# TrinketBlinkM0L.net
KiCad netlist of a schematic drawn in EAGLE
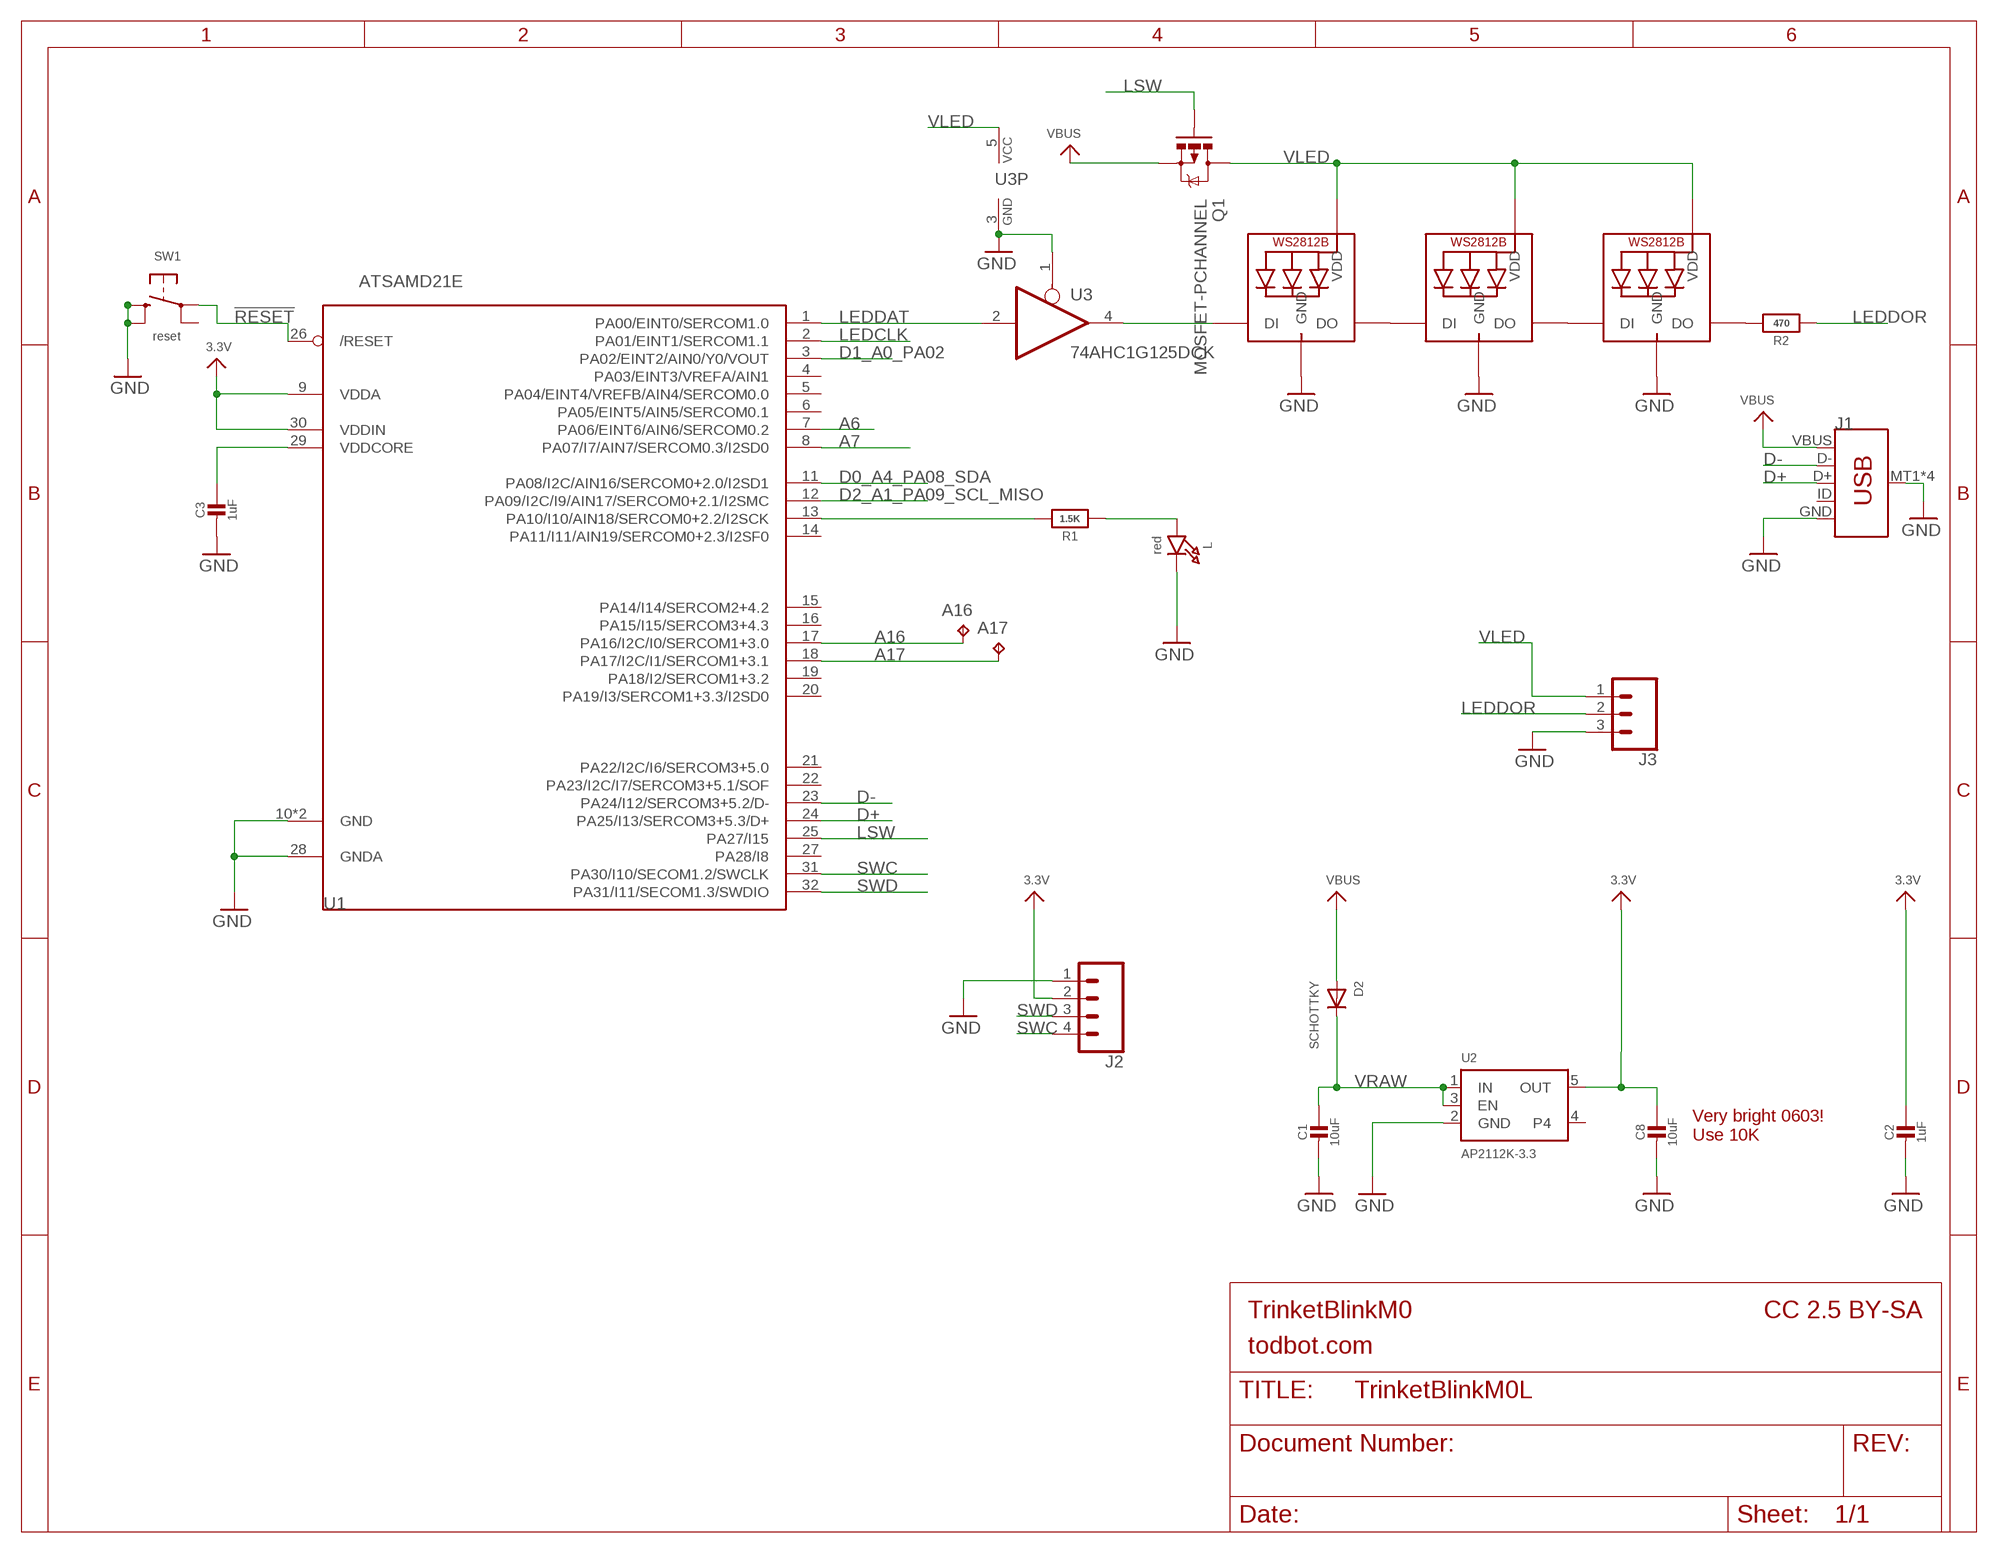
[diagram p0: schematic, sheet 1]

(export (version "E")
  (design (tool "Eeschema 10.0.6"))
  (components
    (comp (ref "A16")
      (value "TPB1,27")
      (footprint "eagle-import:B1,27")
      (libsource (lib "eagle-import") (part "TPB1,27"))
    )
    (comp (ref "A17")
      (value "TPB1,27")
      (footprint "eagle-import:B1,27")
      (libsource (lib "eagle-import") (part "TPB1,27"))
    )
    (comp (ref "C1")
      (value "10uF")
      (footprint "eagle-import:0805-NO")
      (libsource (lib "eagle-import") (part "CAP_CERAMIC0805-NOOUTLINE"))
    )
    (comp (ref "C2")
      (value "1uF")
      (footprint "eagle-import:0603-NO")
      (libsource (lib "eagle-import") (part "CAP_CERAMIC0603_NO"))
    )
    (comp (ref "C3")
      (value "1uF")
      (footprint "eagle-import:0603-NO")
      (libsource (lib "eagle-import") (part "CAP_CERAMIC0603_NO"))
    )
    (comp (ref "C8")
      (value "10uF")
      (footprint "eagle-import:0805-NO")
      (libsource (lib "eagle-import") (part "CAP_CERAMIC0805-NOOUTLINE"))
    )
    (comp (ref "D2")
      (value "SCHOTTKY")
      (footprint "eagle-import:SOD-123FL")
      (libsource (lib "eagle-import") (part "DIODE_SOD-123FL"))
    )
    (comp (ref "J1")
      (value "USB_MICRO-B_SMT")
      (footprint "eagle-import:USB-MICROB")
      (libsource (lib "eagle-import") (part "USB_MICRO-B_SMT"))
    )
    (comp (ref "J2")
      (value "CONN_04")
      (footprint "eagle-import:1X04")
      (libsource (lib "eagle-import") (part "CONN_04"))
    )
    (comp (ref "J3")
      (value "CONN_03")
      (footprint "eagle-import:1X03")
      (libsource (lib "eagle-import") (part "CONN_03"))
    )
    (comp (ref "L")
      (value "red")
      (footprint "eagle-import:CHIPLED_0603_NOOUTLINE")
      (libsource (lib "eagle-import") (part "LED0603_NOOUTLINE"))
    )
    (comp (ref "LED1")
      (value "WS2812B3535")
      (footprint "eagle-import:LED3535")
      (libsource (lib "eagle-import") (part "WS2812B3535"))
    )
    (comp (ref "LED2")
      (value "WS2812B3535")
      (footprint "eagle-import:LED3535")
      (libsource (lib "eagle-import") (part "WS2812B3535"))
    )
    (comp (ref "LED3")
      (value "WS2812B3535")
      (footprint "eagle-import:LED3535")
      (libsource (lib "eagle-import") (part "WS2812B3535"))
    )
    (comp (ref "Q1")
      (value "MOSFET-PCHANNEL")
      (footprint "eagle-import:SOT23-3")
      (libsource (lib "eagle-import") (part "MOSFET-PCHANNEL"))
    )
    (comp (ref "R1")
      (value "1.5K")
      (footprint "eagle-import:0603-NO")
      (libsource (lib "eagle-import") (part "RESISTOR_0603_NOOUT"))
    )
    (comp (ref "R2")
      (value "470")
      (footprint "eagle-import:0603-NO")
      (libsource (lib "eagle-import") (part "RESISTOR_0603_NOOUT"))
    )
    (comp (ref "SW1")
      (value "reset")
      (footprint "eagle-import:BTN_KMR2_4.6X2.8")
      (libsource (lib "eagle-import") (part "SWITCH_TACT_SMT4.6X2.8"))
    )
    (comp (ref "U1")
      (value "ATSAMD21E")
      (footprint "eagle-import:QFN32_5MM")
      (libsource (lib "eagle-import") (part "ATSAMD21E"))
    )
    (comp (ref "U2")
      (value "AP2112K-3.3")
      (footprint "eagle-import:SOT23-5")
      (libsource (lib "eagle-import") (part "VREG_SOT23-5"))
    )
    (comp (ref "U3")
      (value "74AHC1G125DCK")
      (footprint "eagle-import:SC70-5")
      (libsource (lib "eagle-import") (part "741G125DCKAHC"))
    )
  )
  (nets
    (net (code "1") (name "/A6") (class "Default")
      (node (ref "U1") (pin "7") (pinfunction "PA06/EINT6/AIN6/SERCOM0.2_7") (pintype "bidirectional"))
    )
    (net (code "2") (name "/A7") (class "Default")
      (node (ref "U1") (pin "8") (pinfunction "PA07/I7/AIN7/SERCOM0.3/I2SD0_8") (pintype "bidirectional"))
    )
    (net (code "3") (name "/A16") (class "Default")
      (node (ref "A16") (pin "TP") (pinfunction "TP_TP") (pintype "input"))
      (node (ref "U1") (pin "17") (pinfunction "PA16/I2C/I0/SERCOM1+3.0_17") (pintype "bidirectional"))
    )
    (net (code "4") (name "/A17") (class "Default")
      (node (ref "A17") (pin "TP") (pinfunction "TP_TP") (pintype "input"))
      (node (ref "U1") (pin "18") (pinfunction "PA17/I2C/I1/SERCOM1+3.1_18") (pintype "bidirectional"))
    )
    (net (code "5") (name "/D+") (class "Default")
      (node (ref "J1") (pin "D+") (pinfunction "D+_D+") (pintype "bidirectional"))
      (node (ref "U1") (pin "24") (pinfunction "PA25/I13/SERCOM3+5.3/D+_24") (pintype "bidirectional"))
    )
    (net (code "6") (name "/D-") (class "Default")
      (node (ref "J1") (pin "D-") (pinfunction "D-_D-") (pintype "bidirectional"))
      (node (ref "U1") (pin "23") (pinfunction "PA24/I12/SERCOM3+5.2/D-_23") (pintype "bidirectional"))
    )
    (net (code "7") (name "/D0_A4_PA08_SDA") (class "Default")
      (node (ref "U1") (pin "11") (pinfunction "PA08/I2C/AIN16/SERCOM0+2.0/I2SD1_11") (pintype "bidirectional"))
    )
    (net (code "8") (name "/D1_A0_PA02") (class "Default")
      (node (ref "U1") (pin "3") (pinfunction "PA02/EINT2/AIN0/Y0/VOUT_3") (pintype "bidirectional"))
    )
    (net (code "9") (name "/D2_A1_PA09_SCL_MISO") (class "Default")
      (node (ref "U1") (pin "12") (pinfunction "PA09/I2C/I9/AIN17/SERCOM0+2.1/I2SMC_12") (pintype "bidirectional"))
    )
    (net (code "10") (name "/LEDCLK") (class "Default")
      (node (ref "U1") (pin "2") (pinfunction "PA01/EINT1/SERCOM1.1_2") (pintype "bidirectional"))
    )
    (net (code "11") (name "/LEDDAT") (class "Default")
      (node (ref "U1") (pin "1") (pinfunction "PA00/EINT0/SERCOM1.0_1") (pintype "bidirectional"))
      (node (ref "U3") (pin "2") (pinfunction "I_2") (pintype "input"))
    )
    (net (code "12") (name "/LEDDOR") (class "Default")
      (node (ref "J3") (pin "2") (pinfunction "2_2") (pintype "passive"))
      (node (ref "R2") (pin "1") (pinfunction "1_1") (pintype "passive"))
    )
    (net (code "13") (name "/LSW") (class "Default")
      (node (ref "Q1") (pin "1") (pinfunction "G_1") (pintype "passive"))
      (node (ref "U1") (pin "25") (pinfunction "PA27/I15_25") (pintype "bidirectional"))
    )
    (net (code "14") (name "/SWC") (class "Default")
      (node (ref "J2") (pin "4") (pinfunction "4_4") (pintype "passive"))
      (node (ref "U1") (pin "31") (pinfunction "PA30/I10/SECOM1.2/SWCLK_31") (pintype "bidirectional"))
    )
    (net (code "15") (name "/SWD") (class "Default")
      (node (ref "J2") (pin "3") (pinfunction "3_3") (pintype "passive"))
      (node (ref "U1") (pin "32") (pinfunction "PA31/I11/SECOM1.3/SWDIO_32") (pintype "bidirectional"))
    )
    (net (code "16") (name "/VLED") (class "Default")
      (node (ref "J3") (pin "1") (pinfunction "1_1") (pintype "passive"))
      (node (ref "LED1") (pin "2") (pinfunction "VDD_2") (pintype "power_in"))
      (node (ref "LED2") (pin "2") (pinfunction "VDD_2") (pintype "power_in"))
      (node (ref "LED3") (pin "2") (pinfunction "VDD_2") (pintype "power_in"))
      (node (ref "Q1") (pin "3") (pinfunction "D_3") (pintype "passive"))
      (node (ref "U3") (pin "5") (pinfunction "VCC_5") (pintype "power_in"))
    )
    (net (code "17") (name "/VRAW") (class "Default")
      (node (ref "C1") (pin "1") (pinfunction "1_1") (pintype "passive"))
      (node (ref "D2") (pin "C") (pinfunction "C_C") (pintype "passive"))
      (node (ref "U2") (pin "1") (pinfunction "IN_1") (pintype "power_in"))
      (node (ref "U2") (pin "3") (pinfunction "EN_3") (pintype "input"))
    )
    (net (code "18") (name "/~{RESET}") (class "Default")
      (node (ref "SW1") (pin "A") (pinfunction "P_A") (pintype "passive"))
      (node (ref "U1") (pin "26") (pinfunction "/RESET_26") (pintype "bidirectional"))
    )
    (net (code "19") (name "3.3V") (class "Default")
      (node (ref "C2") (pin "1") (pinfunction "1_1") (pintype "passive"))
      (node (ref "C8") (pin "1") (pinfunction "1_1") (pintype "passive"))
      (node (ref "J2") (pin "2") (pinfunction "2_2") (pintype "passive"))
      (node (ref "U1") (pin "30") (pinfunction "VDDIN_30") (pintype "power_in"))
      (node (ref "U1") (pin "9") (pinfunction "VDDA_9") (pintype "power_in"))
      (node (ref "U2") (pin "5") (pinfunction "OUT_5") (pintype "power_in"))
    )
    (net (code "20") (name "GND") (class "Default")
      (node (ref "C1") (pin "2") (pinfunction "2_2") (pintype "passive"))
      (node (ref "C2") (pin "2") (pinfunction "2_2") (pintype "passive"))
      (node (ref "C3") (pin "2") (pinfunction "2_2") (pintype "passive"))
      (node (ref "C8") (pin "2") (pinfunction "2_2") (pintype "passive"))
      (node (ref "J1") (pin "GND") (pinfunction "GND_GND") (pintype "power_in"))
      (node (ref "J1") (pin "MT1") (pinfunction "SHIELD_MT1") (pintype "bidirectional"))
      (node (ref "J1") (pin "MT2") (pinfunction "SHIELD_MT2") (pintype "bidirectional"))
      (node (ref "J1") (pin "P$1") (pinfunction "SHIELD_P$1") (pintype "bidirectional"))
      (node (ref "J1") (pin "P$2") (pinfunction "SHIELD_P$2") (pintype "bidirectional"))
      (node (ref "J2") (pin "1") (pinfunction "1_1") (pintype "passive"))
      (node (ref "J3") (pin "3") (pinfunction "3_3") (pintype "passive"))
      (node (ref "L") (pin "C") (pinfunction "C_C") (pintype "passive"))
      (node (ref "LED1") (pin "4") (pinfunction "GND_4") (pintype "power_in"))
      (node (ref "LED2") (pin "4") (pinfunction "GND_4") (pintype "power_in"))
      (node (ref "LED3") (pin "4") (pinfunction "GND_4") (pintype "power_in"))
      (node (ref "SW1") (pin "B") (pinfunction "S_B") (pintype "passive"))
      (node (ref "SW1") (pin "B'") (pinfunction "S1_B'") (pintype "passive"))
      (node (ref "U1") (pin "10") (pinfunction "GND_10") (pintype "power_in"))
      (node (ref "U1") (pin "28") (pinfunction "GNDA_28") (pintype "power_in"))
      (node (ref "U1") (pin "33") (pinfunction "GND_33") (pintype "power_in"))
      (node (ref "U2") (pin "2") (pinfunction "GND_2") (pintype "power_in"))
      (node (ref "U3") (pin "1") (pinfunction "OE_1") (pintype "input"))
      (node (ref "U3") (pin "3") (pinfunction "GND_3") (pintype "power_in"))
    )
    (net (code "21") (name "Net-(L-PadA)") (class "Default")
      (node (ref "L") (pin "A") (pinfunction "A_A") (pintype "passive"))
      (node (ref "R1") (pin "1") (pinfunction "1_1") (pintype "passive"))
    )
    (net (code "22") (name "Net-(LED1-DI)") (class "Default")
      (node (ref "LED1") (pin "1") (pinfunction "DI_1") (pintype "input"))
      (node (ref "U3") (pin "4") (pinfunction "O_4") (pintype "tri_state"))
    )
    (net (code "23") (name "Net-(LED1-DO)") (class "Default")
      (node (ref "LED1") (pin "3") (pinfunction "DO_3") (pintype "output"))
      (node (ref "LED2") (pin "1") (pinfunction "DI_1") (pintype "input"))
    )
    (net (code "24") (name "Net-(LED2-DO)") (class "Default")
      (node (ref "LED2") (pin "3") (pinfunction "DO_3") (pintype "output"))
      (node (ref "LED3") (pin "1") (pinfunction "DI_1") (pintype "input"))
    )
    (net (code "25") (name "Net-(LED3-DO)") (class "Default")
      (node (ref "LED3") (pin "3") (pinfunction "DO_3") (pintype "output"))
      (node (ref "R2") (pin "2") (pinfunction "2_2") (pintype "passive"))
    )
    (net (code "26") (name "Net-(U1-PA10{slash}I10{slash}AIN18{slash}SERCOM0+2.2{slash}I2SCK)") (class "Default")
      (node (ref "R1") (pin "2") (pinfunction "2_2") (pintype "passive"))
      (node (ref "U1") (pin "13") (pinfunction "PA10/I10/AIN18/SERCOM0+2.2/I2SCK_13") (pintype "bidirectional"))
    )
    (net (code "27") (name "Net-(U1-VDDCORE)") (class "Default")
      (node (ref "C3") (pin "1") (pinfunction "1_1") (pintype "passive"))
      (node (ref "U1") (pin "29") (pinfunction "VDDCORE_29") (pintype "power_in"))
    )
    (net (code "28") (name "VBUS") (class "Default")
      (node (ref "D2") (pin "A") (pinfunction "A_A") (pintype "passive"))
      (node (ref "J1") (pin "VBUS") (pinfunction "VBUS_VBUS") (pintype "power_in"))
      (node (ref "Q1") (pin "2") (pinfunction "S_2") (pintype "passive"))
    )
    (net (code "29") (name "unconnected-(J1-PadID)") (class "Default")
      (node (ref "J1") (pin "ID") (pinfunction "ID_ID") (pintype "bidirectional"))
    )
    (net (code "30") (name "unconnected-(SW1-P1-PadA')") (class "Default")
      (node (ref "SW1") (pin "A'") (pinfunction "P1_A'") (pintype "passive"))
    )
    (net (code "31") (name "unconnected-(U1-PA03{slash}EINT3{slash}VREFA{slash}AIN1-Pad4)") (class "Default")
      (node (ref "U1") (pin "4") (pinfunction "PA03/EINT3/VREFA/AIN1_4") (pintype "bidirectional"))
    )
    (net (code "32") (name "unconnected-(U1-PA04{slash}EINT4{slash}VREFB{slash}AIN4{slash}SERCOM0.0-Pad5)") (class "Default")
      (node (ref "U1") (pin "5") (pinfunction "PA04/EINT4/VREFB/AIN4/SERCOM0.0_5") (pintype "bidirectional"))
    )
    (net (code "33") (name "unconnected-(U1-PA05{slash}EINT5{slash}AIN5{slash}SERCOM0.1-Pad6)") (class "Default")
      (node (ref "U1") (pin "6") (pinfunction "PA05/EINT5/AIN5/SERCOM0.1_6") (pintype "bidirectional"))
    )
    (net (code "34") (name "unconnected-(U1-PA11{slash}I11{slash}AIN19{slash}SERCOM0+2.3{slash}I2SF0-Pad14)") (class "Default")
      (node (ref "U1") (pin "14") (pinfunction "PA11/I11/AIN19/SERCOM0+2.3/I2SF0_14") (pintype "bidirectional"))
    )
    (net (code "35") (name "unconnected-(U1-PA14{slash}I14{slash}SERCOM2+4.2-Pad15)") (class "Default")
      (node (ref "U1") (pin "15") (pinfunction "PA14/I14/SERCOM2+4.2_15") (pintype "bidirectional"))
    )
    (net (code "36") (name "unconnected-(U1-PA15{slash}I15{slash}SERCOM3+4.3-Pad16)") (class "Default")
      (node (ref "U1") (pin "16") (pinfunction "PA15/I15/SERCOM3+4.3_16") (pintype "bidirectional"))
    )
    (net (code "37") (name "unconnected-(U1-PA18{slash}I2{slash}SERCOM1+3.2-Pad19)") (class "Default")
      (node (ref "U1") (pin "19") (pinfunction "PA18/I2/SERCOM1+3.2_19") (pintype "bidirectional"))
    )
    (net (code "38") (name "unconnected-(U1-PA19{slash}I3{slash}SERCOM1+3.3{slash}I2SD0-Pad20)") (class "Default")
      (node (ref "U1") (pin "20") (pinfunction "PA19/I3/SERCOM1+3.3/I2SD0_20") (pintype "bidirectional"))
    )
    (net (code "39") (name "unconnected-(U1-PA22{slash}I2C{slash}I6{slash}SERCOM3+5.0-Pad21)") (class "Default")
      (node (ref "U1") (pin "21") (pinfunction "PA22/I2C/I6/SERCOM3+5.0_21") (pintype "bidirectional"))
    )
    (net (code "40") (name "unconnected-(U1-PA23{slash}I2C{slash}I7{slash}SERCOM3+5.1{slash}SOF-Pad22)") (class "Default")
      (node (ref "U1") (pin "22") (pinfunction "PA23/I2C/I7/SERCOM3+5.1/SOF_22") (pintype "bidirectional"))
    )
    (net (code "41") (name "unconnected-(U1-PA28{slash}I8-Pad27)") (class "Default")
      (node (ref "U1") (pin "27") (pinfunction "PA28/I8_27") (pintype "bidirectional"))
    )
    (net (code "42") (name "unconnected-(U2-P4-Pad4)") (class "Default")
      (node (ref "U2") (pin "4") (pinfunction "P4_4") (pintype "bidirectional"))
    )
  )
)
